# Sheet.net
KiCad netlist of a schematic drawn in Altium Designer
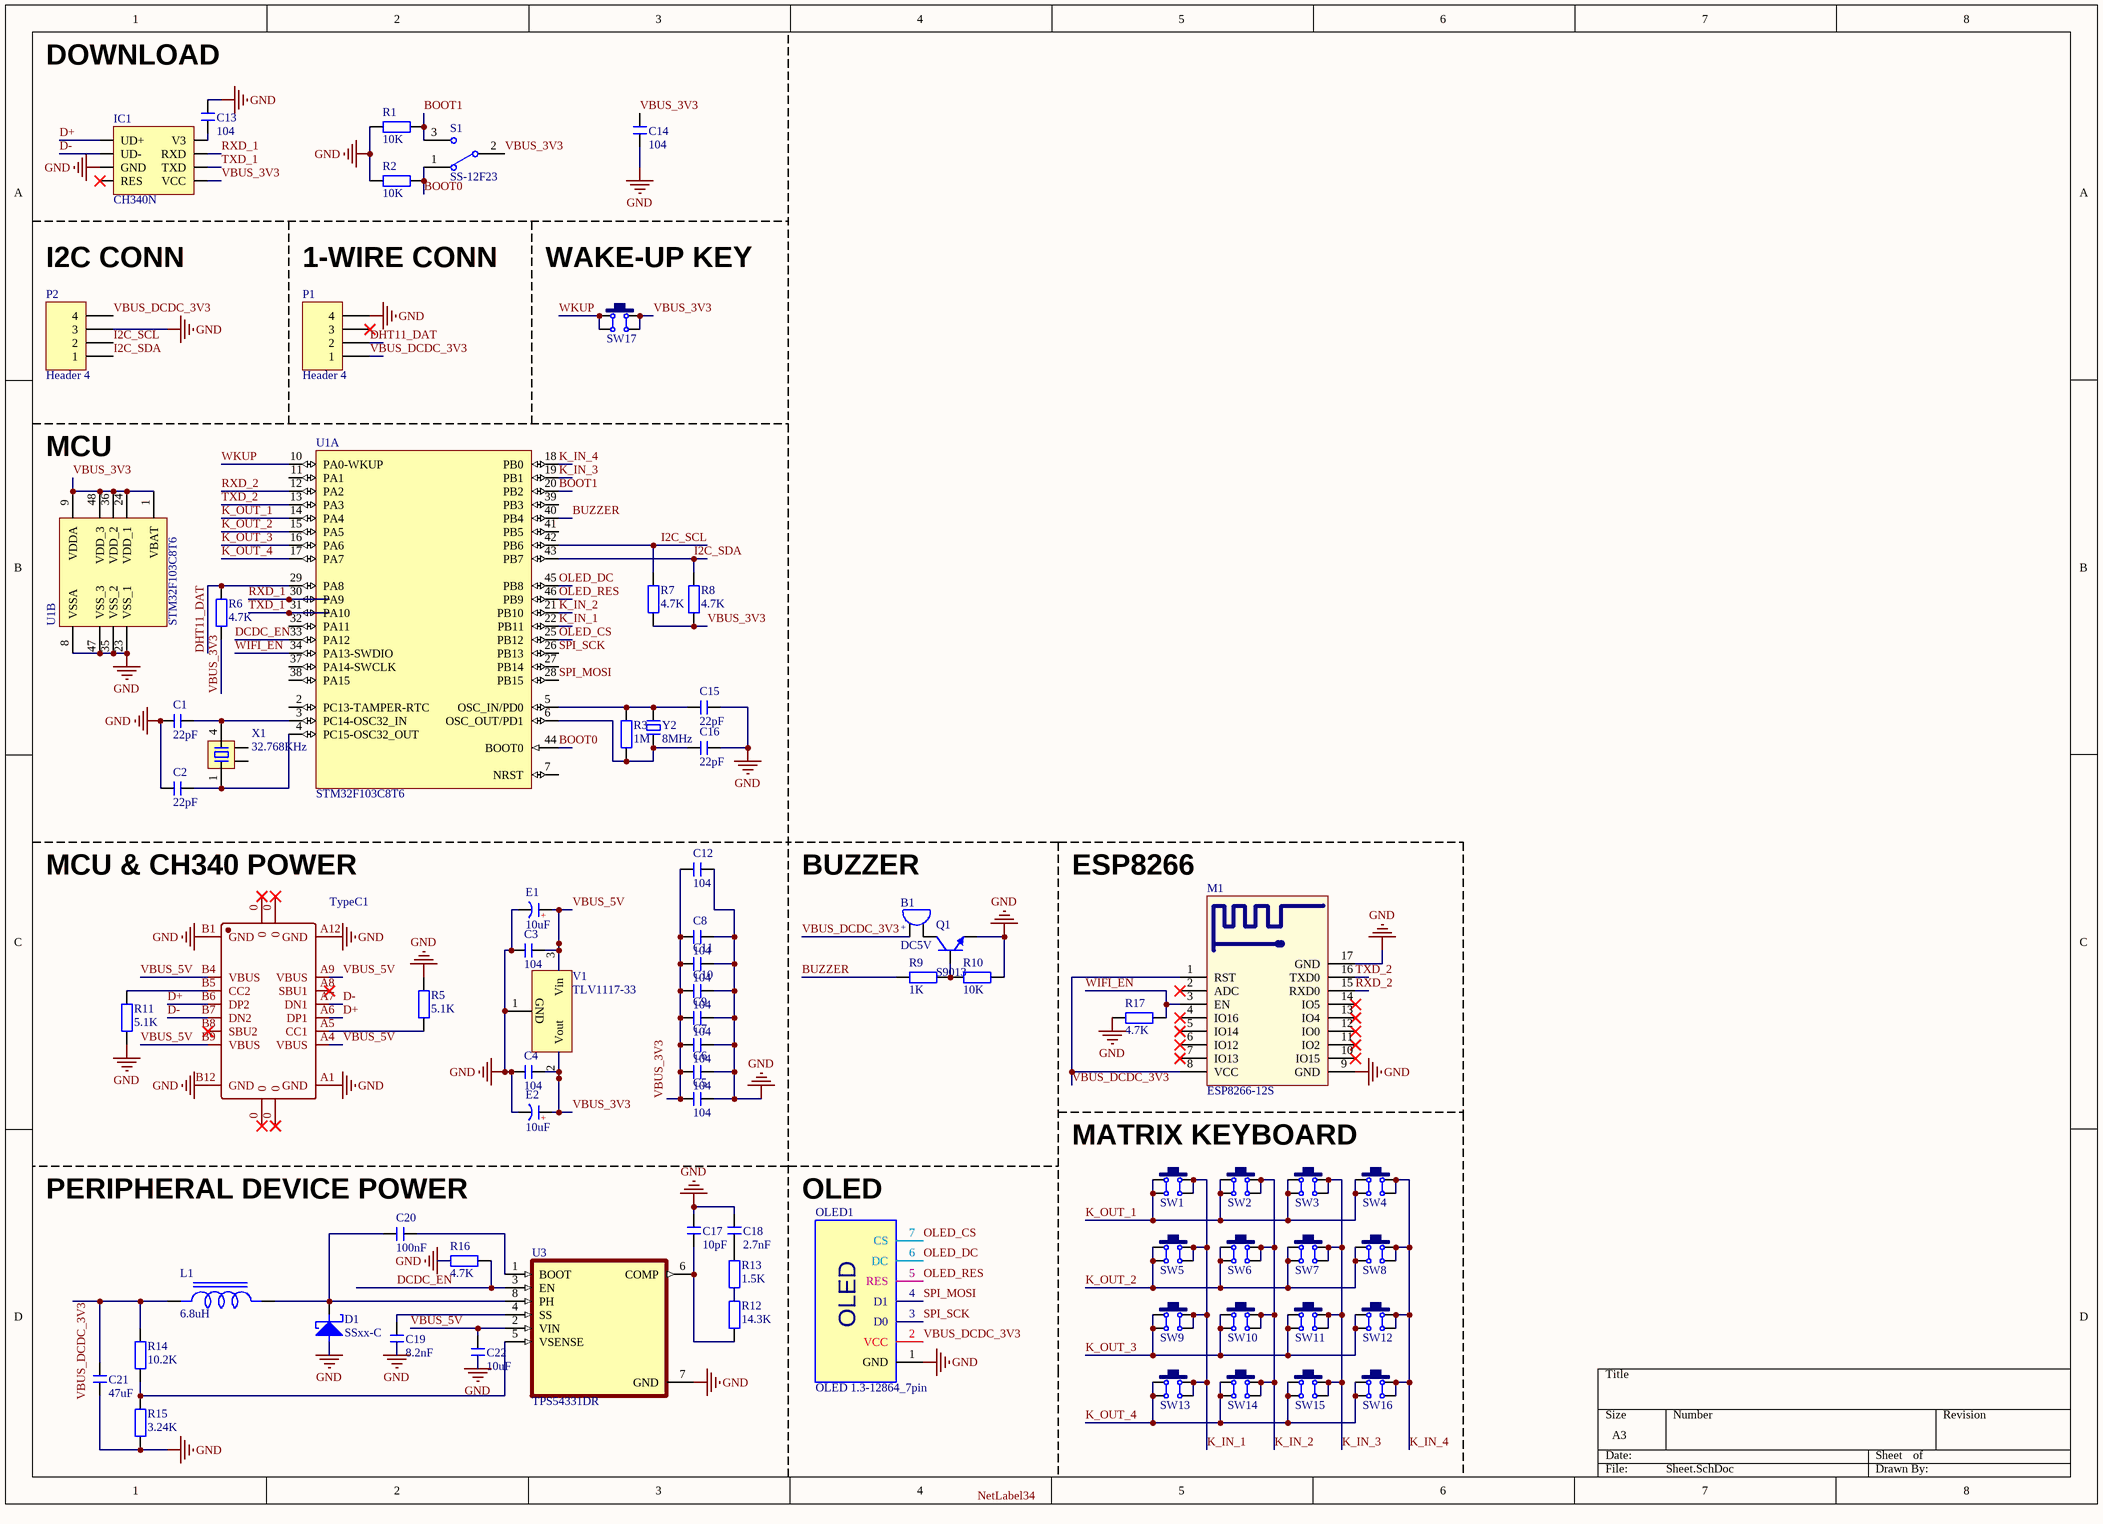
[diagram p0: Sheet.SchDoc]

(export (version "E")
  (design (tool "Eeschema 10.0.6"))
  (components
    (comp (ref "B1")
      (value "DC5V")
      (footprint "BEEP 5x9x5.5")
      (description "蜂鸣器")
      (fields (field (name "版权归属") "黎明电子style"))
      (libsource (lib "基地硬件部AD库3.01") (part "BEEP"))
    )
    (comp (ref "C1")
      (value "22pF")
      (footprint "C 0805")
      (description "无极性贴片电容")
      (fields (field (name "版权归属") "黎明电子style"))
      (libsource (lib "基地硬件部AD库3.01") (part "C"))
    )
    (comp (ref "C2")
      (value "22pF")
      (footprint "C 0805")
      (description "无极性贴片电容")
      (fields (field (name "版权归属") "黎明电子style"))
      (libsource (lib "基地硬件部AD库3.01") (part "C"))
    )
    (comp (ref "C3")
      (value "104")
      (footprint "C 0805")
      (description "无极性贴片电容")
      (fields (field (name "版权归属") "黎明电子style"))
      (libsource (lib "基地硬件部AD库3.01") (part "C"))
    )
    (comp (ref "C4")
      (value "104")
      (footprint "C 0805")
      (description "无极性贴片电容")
      (fields (field (name "版权归属") "黎明电子style"))
      (libsource (lib "基地硬件部AD库3.01") (part "C"))
    )
    (comp (ref "C5")
      (value "104")
      (footprint "C 0805")
      (description "无极性贴片电容")
      (fields (field (name "版权归属") "黎明电子style"))
      (libsource (lib "基地硬件部AD库3.01") (part "C"))
    )
    (comp (ref "C6")
      (value "104")
      (footprint "C 0805")
      (description "无极性贴片电容")
      (fields (field (name "版权归属") "黎明电子style"))
      (libsource (lib "基地硬件部AD库3.01") (part "C"))
    )
    (comp (ref "C7")
      (value "104")
      (footprint "C 0805")
      (description "无极性贴片电容")
      (fields (field (name "版权归属") "黎明电子style"))
      (libsource (lib "基地硬件部AD库3.01") (part "C"))
    )
    (comp (ref "C8")
      (value "104")
      (footprint "C 0805")
      (description "无极性贴片电容")
      (fields (field (name "版权归属") "黎明电子style"))
      (libsource (lib "基地硬件部AD库3.01") (part "C"))
    )
    (comp (ref "C9")
      (value "104")
      (footprint "C 0805")
      (description "无极性贴片电容")
      (fields (field (name "版权归属") "黎明电子style"))
      (libsource (lib "基地硬件部AD库3.01") (part "C"))
    )
    (comp (ref "C10")
      (value "104")
      (footprint "C 0805")
      (description "无极性贴片电容")
      (fields (field (name "版权归属") "黎明电子style"))
      (libsource (lib "基地硬件部AD库3.01") (part "C"))
    )
    (comp (ref "C11")
      (value "104")
      (footprint "C 0805")
      (description "无极性贴片电容")
      (fields (field (name "版权归属") "黎明电子style"))
      (libsource (lib "基地硬件部AD库3.01") (part "C"))
    )
    (comp (ref "C12")
      (value "104")
      (footprint "C 0805")
      (description "无极性贴片电容")
      (fields (field (name "版权归属") "黎明电子style"))
      (libsource (lib "基地硬件部AD库3.01") (part "C"))
    )
    (comp (ref "C13")
      (value "104")
      (footprint "C 0805")
      (description "无极性贴片电容")
      (fields (field (name "版权归属") "黎明电子style"))
      (libsource (lib "基地硬件部AD库3.01") (part "C"))
    )
    (comp (ref "C14")
      (value "104")
      (footprint "C 0805")
      (description "无极性贴片电容")
      (fields (field (name "版权归属") "黎明电子style"))
      (libsource (lib "基地硬件部AD库3.01") (part "C"))
    )
    (comp (ref "C15")
      (value "22pF")
      (footprint "C 0805")
      (description "无极性贴片电容")
      (fields (field (name "版权归属") "黎明电子style"))
      (libsource (lib "基地硬件部AD库3.01") (part "C"))
    )
    (comp (ref "C16")
      (value "22pF")
      (footprint "C 0805")
      (description "无极性贴片电容")
      (fields (field (name "版权归属") "黎明电子style"))
      (libsource (lib "基地硬件部AD库3.01") (part "C"))
    )
    (comp (ref "C17")
      (value "10pF")
      (footprint "C 0805")
      (description "无极性贴片电容")
      (fields (field (name "版权归属") "黎明电子style"))
      (libsource (lib "基地硬件部AD库3.01") (part "C"))
    )
    (comp (ref "C18")
      (value "2.7nF")
      (footprint "C 0805")
      (description "无极性贴片电容")
      (fields (field (name "版权归属") "黎明电子style"))
      (libsource (lib "基地硬件部AD库3.01") (part "C"))
    )
    (comp (ref "C19")
      (value "8.2nF")
      (footprint "C 0805")
      (description "无极性贴片电容")
      (fields (field (name "版权归属") "黎明电子style"))
      (libsource (lib "基地硬件部AD库3.01") (part "C"))
    )
    (comp (ref "C20")
      (value "100nF")
      (footprint "C 0805")
      (description "无极性贴片电容")
      (fields (field (name "版权归属") "黎明电子style"))
      (libsource (lib "基地硬件部AD库3.01") (part "C"))
    )
    (comp (ref "C21")
      (value "47uF")
      (footprint "C 0805")
      (description "无极性贴片电容")
      (fields (field (name "版权归属") "黎明电子style"))
      (libsource (lib "基地硬件部AD库3.01") (part "C"))
    )
    (comp (ref "C22")
      (value "10uF")
      (footprint "C 0805")
      (description "无极性贴片电容")
      (fields (field (name "版权归属") "黎明电子style"))
      (libsource (lib "基地硬件部AD库3.01") (part "C"))
    )
    (comp (ref "D1")
      (value "SSxx-C")
      (footprint "SMA")
      (description "肖特基二极管-贴片")
      (libsource (lib "基地硬件部AD库3.01") (part "SSxx-C"))
    )
    (comp (ref "E1")
      (value "10uF")
      (footprint "CD A(3216)")
      (description "贴片钽电容")
      (fields (field (name "版权归属") "黎明电子style"))
      (libsource (lib "基地硬件部AD库3.01") (part "C-CD"))
    )
    (comp (ref "E2")
      (value "10uF")
      (footprint "CD A(3216)")
      (description "贴片钽电容")
      (fields (field (name "版权归属") "黎明电子style"))
      (libsource (lib "基地硬件部AD库3.01") (part "C-CD"))
    )
    (comp (ref "IC1")
      (value "CH340N")
      (footprint "SOP8_N")
      (description "串口转USB")
      (fields (field (name "版权归属") "黎明电子style"))
      (libsource (lib "基地硬件部AD库3.01") (part "CH340N"))
    )
    (comp (ref "L1")
      (value "6.8uH")
      (footprint "IND_SRR4818A-6R8Y")
      (fields (field (name "MP") "SRR4818A-6R8Y"))
      (libsource (lib "SRR4818A-6R8Y") (part "SRR4818A-6R8Y"))
    )
    (comp (ref "M1")
      (value "ESP8266-12S")
      (footprint "ESP-12S Module")
      (description "串口WIFI模块，ESP8266-12S")
      (libsource (lib "基地硬件部AD库3.01") (part "ESP8266-12S"))
    )
    (comp (ref "OLED1")
      (value "OLED 1.3-12864_7pin")
      (footprint "OLED 1.3-12864_7pin")
      (description "OLED-SPI")
      (libsource (lib "基地硬件部AD库3.01") (part "OLED-1.3-SPI"))
    )
    (comp (ref "P1")
      (value "Header 4")
      (footprint "HDR1X4")
      (description "Header, 4-Pin")
      (fields (field (name "PUBLISHER") "Altium Limited"))
      (libsource (lib "Miscellaneous Connectors") (part "Header 4"))
    )
    (comp (ref "P2")
      (value "Header 4")
      (footprint "HDR1X4")
      (description "Header, 4-Pin")
      (fields (field (name "PUBLISHER") "Altium Limited"))
      (libsource (lib "Miscellaneous Connectors") (part "Header 4"))
    )
    (comp (ref "Q1")
      (value "S9013")
      (footprint "SOT23-3N")
      (description "低频放大-NPN型")
      (fields (field (name "版权归属") "源创客"))
      (libsource (lib "基地硬件部AD库3.01") (part "9013-SMD"))
    )
    (comp (ref "R1")
      (value "10K")
      (footprint "R 0805")
      (description "贴片电阻")
      (fields (field (name "版权归属") "黎明电子style"))
      (libsource (lib "基地硬件部AD库3.01") (part "R"))
    )
    (comp (ref "R2")
      (value "10K")
      (footprint "R 0805")
      (description "贴片电阻")
      (fields (field (name "版权归属") "黎明电子style"))
      (libsource (lib "基地硬件部AD库3.01") (part "R"))
    )
    (comp (ref "R3")
      (value "1M")
      (footprint "R 0805")
      (description "贴片电阻")
      (fields (field (name "版权归属") "黎明电子style"))
      (libsource (lib "基地硬件部AD库3.01") (part "R"))
    )
    (comp (ref "R5")
      (value "5.1K")
      (footprint "R 0805")
      (description "贴片电阻")
      (fields (field (name "版权归属") "黎明电子style"))
      (libsource (lib "基地硬件部AD库3.01") (part "R"))
    )
    (comp (ref "R6")
      (value "4.7K")
      (footprint "R 0805")
      (description "贴片电阻")
      (fields (field (name "版权归属") "黎明电子style"))
      (libsource (lib "基地硬件部AD库3.01") (part "R"))
    )
    (comp (ref "R7")
      (value "4.7K")
      (footprint "R 0805")
      (description "贴片电阻")
      (fields (field (name "版权归属") "黎明电子style"))
      (libsource (lib "基地硬件部AD库3.01") (part "R"))
    )
    (comp (ref "R8")
      (value "4.7K")
      (footprint "R 0805")
      (description "贴片电阻")
      (fields (field (name "版权归属") "黎明电子style"))
      (libsource (lib "基地硬件部AD库3.01") (part "R"))
    )
    (comp (ref "R9")
      (value "1K")
      (footprint "R 0805")
      (description "贴片电阻")
      (fields (field (name "版权归属") "黎明电子style"))
      (libsource (lib "基地硬件部AD库3.01") (part "R"))
    )
    (comp (ref "R10")
      (value "10K")
      (footprint "R 0805")
      (description "贴片电阻")
      (fields (field (name "版权归属") "黎明电子style"))
      (libsource (lib "基地硬件部AD库3.01") (part "R"))
    )
    (comp (ref "R11")
      (value "5.1K")
      (footprint "R 0805")
      (description "贴片电阻")
      (fields (field (name "版权归属") "黎明电子style"))
      (libsource (lib "基地硬件部AD库3.01") (part "R"))
    )
    (comp (ref "R12")
      (value "14.3K")
      (footprint "R 0805")
      (description "贴片电阻")
      (fields (field (name "版权归属") "黎明电子style"))
      (libsource (lib "基地硬件部AD库3.01") (part "R"))
    )
    (comp (ref "R13")
      (value "1.5K")
      (footprint "R 0805")
      (description "贴片电阻")
      (fields (field (name "版权归属") "黎明电子style"))
      (libsource (lib "基地硬件部AD库3.01") (part "R"))
    )
    (comp (ref "R14")
      (value "10.2K")
      (footprint "R 0805")
      (description "贴片电阻")
      (fields (field (name "版权归属") "黎明电子style"))
      (libsource (lib "基地硬件部AD库3.01") (part "R"))
    )
    (comp (ref "R15")
      (value "3.24K")
      (footprint "R 0805")
      (description "贴片电阻")
      (fields (field (name "版权归属") "黎明电子style"))
      (libsource (lib "基地硬件部AD库3.01") (part "R"))
    )
    (comp (ref "R16")
      (value "4.7K")
      (footprint "R 0805")
      (description "贴片电阻")
      (fields (field (name "版权归属") "黎明电子style"))
      (libsource (lib "基地硬件部AD库3.01") (part "R"))
    )
    (comp (ref "R17")
      (value "4.7K")
      (footprint "R 0805")
      (description "贴片电阻")
      (fields (field (name "版权归属") "黎明电子style"))
      (libsource (lib "基地硬件部AD库3.01") (part "R"))
    )
    (comp (ref "S1")
      (value "SS-12F23")
      (footprint "MSK-12C01-07")
      (description "1路波动开关")
      (fields (field (name "版权归属") "黎明电子style"))
      (libsource (lib "基地硬件部AD库3.01") (part "SSW-1P"))
    )
    (comp (ref "SW1")
      (value "6x6x5")
      (footprint "TSW SMD-6*6*4.3")
      (description "贴片6x6轻触开关")
      (fields (field (name "版权归属") "黎明电子style"))
      (libsource (lib "基地硬件部AD库3.01") (part "TSW SMD-6x6"))
    )
    (comp (ref "SW2")
      (value "6x6x5")
      (footprint "TSW SMD-6*6*4.3")
      (description "贴片6x6轻触开关")
      (fields (field (name "版权归属") "黎明电子style"))
      (libsource (lib "基地硬件部AD库3.01") (part "TSW SMD-6x6"))
    )
    (comp (ref "SW3")
      (value "6x6x5")
      (footprint "TSW SMD-6*6*4.3")
      (description "贴片6x6轻触开关")
      (fields (field (name "版权归属") "黎明电子style"))
      (libsource (lib "基地硬件部AD库3.01") (part "TSW SMD-6x6"))
    )
    (comp (ref "SW4")
      (value "6x6x5")
      (footprint "TSW SMD-6*6*4.3")
      (description "贴片6x6轻触开关")
      (fields (field (name "版权归属") "黎明电子style"))
      (libsource (lib "基地硬件部AD库3.01") (part "TSW SMD-6x6"))
    )
    (comp (ref "SW5")
      (value "6x6x5")
      (footprint "TSW SMD-6*6*4.3")
      (description "贴片6x6轻触开关")
      (fields (field (name "版权归属") "黎明电子style"))
      (libsource (lib "基地硬件部AD库3.01") (part "TSW SMD-6x6"))
    )
    (comp (ref "SW6")
      (value "6x6x5")
      (footprint "TSW SMD-6*6*4.3")
      (description "贴片6x6轻触开关")
      (fields (field (name "版权归属") "黎明电子style"))
      (libsource (lib "基地硬件部AD库3.01") (part "TSW SMD-6x6"))
    )
    (comp (ref "SW7")
      (value "6x6x5")
      (footprint "TSW SMD-6*6*4.3")
      (description "贴片6x6轻触开关")
      (fields (field (name "版权归属") "黎明电子style"))
      (libsource (lib "基地硬件部AD库3.01") (part "TSW SMD-6x6"))
    )
    (comp (ref "SW8")
      (value "6x6x5")
      (footprint "TSW SMD-6*6*4.3")
      (description "贴片6x6轻触开关")
      (fields (field (name "版权归属") "黎明电子style"))
      (libsource (lib "基地硬件部AD库3.01") (part "TSW SMD-6x6"))
    )
    (comp (ref "SW9")
      (value "6x6x5")
      (footprint "TSW SMD-6*6*4.3")
      (description "贴片6x6轻触开关")
      (fields (field (name "版权归属") "黎明电子style"))
      (libsource (lib "基地硬件部AD库3.01") (part "TSW SMD-6x6"))
    )
    (comp (ref "SW10")
      (value "6x6x5")
      (footprint "TSW SMD-6*6*4.3")
      (description "贴片6x6轻触开关")
      (fields (field (name "版权归属") "黎明电子style"))
      (libsource (lib "基地硬件部AD库3.01") (part "TSW SMD-6x6"))
    )
    (comp (ref "SW11")
      (value "6x6x5")
      (footprint "TSW SMD-6*6*4.3")
      (description "贴片6x6轻触开关")
      (fields (field (name "版权归属") "黎明电子style"))
      (libsource (lib "基地硬件部AD库3.01") (part "TSW SMD-6x6"))
    )
    (comp (ref "SW12")
      (value "6x6x5")
      (footprint "TSW SMD-6*6*4.3")
      (description "贴片6x6轻触开关")
      (fields (field (name "版权归属") "黎明电子style"))
      (libsource (lib "基地硬件部AD库3.01") (part "TSW SMD-6x6"))
    )
    (comp (ref "SW13")
      (value "6x6x5")
      (footprint "TSW SMD-6*6*4.3")
      (description "贴片6x6轻触开关")
      (fields (field (name "版权归属") "黎明电子style"))
      (libsource (lib "基地硬件部AD库3.01") (part "TSW SMD-6x6"))
    )
    (comp (ref "SW14")
      (value "6x6x5")
      (footprint "TSW SMD-6*6*4.3")
      (description "贴片6x6轻触开关")
      (fields (field (name "版权归属") "黎明电子style"))
      (libsource (lib "基地硬件部AD库3.01") (part "TSW SMD-6x6"))
    )
    (comp (ref "SW15")
      (value "6x6x5")
      (footprint "TSW SMD-6*6*4.3")
      (description "贴片6x6轻触开关")
      (fields (field (name "版权归属") "黎明电子style"))
      (libsource (lib "基地硬件部AD库3.01") (part "TSW SMD-6x6"))
    )
    (comp (ref "SW16")
      (value "6x6x5")
      (footprint "TSW SMD-6*6*4.3")
      (description "贴片6x6轻触开关")
      (fields (field (name "版权归属") "黎明电子style"))
      (libsource (lib "基地硬件部AD库3.01") (part "TSW SMD-6x6"))
    )
    (comp (ref "SW17")
      (value "6x6x5")
      (footprint "TSW SMD-6*6*4.3")
      (description "贴片6x6轻触开关")
      (fields (field (name "版权归属") "黎明电子style"))
      (libsource (lib "基地硬件部AD库3.01") (part "TSW SMD-6x6"))
    )
    (comp (ref "TypeC1")
      (value "TypeC-16pin")
      (footprint "typeC-16pin")
      (description "USB-C-16Pin")
      (libsource (lib "基地硬件部AD库3.01") (part "TypeC-16pin"))
    )
    (comp (ref "U1")
      (value "STM32F103C8T6")
      (footprint "LQFP48 7X7_N")
      (description "Pin:48/IO:36")
      (fields (field (name "版权归属") "校基地硬件部"))
      (libsource (lib "") (part "STM32F103C8Tx_1"))
    )
    (comp (ref "U3")
      (value "TPS54331DR")
      (footprint "SOIC127P599X175-8N")
      (description "3.5V to 28V Input, 3A, 570kHz Step-Down Converter with Eco-mode 8-SOIC -40 to 150")
      (fields (field (name "MF") "Texas Instruments"))
      (libsource (lib "TPS54331DR") (part "TPS54331DR"))
    )
    (comp (ref "V1")
      (value "TLV1117-33")
      (footprint "SOT223_L")
      (description "三端稳压芯片")
      (fields (field (name "版权归属") "源创客"))
      (libsource (lib "基地硬件部AD库3.01") (part "AMS1117"))
    )
    (comp (ref "X1")
      (value "32.768KHz")
      (footprint "OSC MC-146")
      (description "MC系列4脚晶振")
      (fields (field (name "版权归属") "源创客"))
      (libsource (lib "基地硬件部AD库3.01") (part "XTAL-MC-4P"))
    )
    (comp (ref "Y2")
      (value "8MHz")
      (footprint "OSC HC-49SMD")
      (description "2脚无源脚晶振")
      (fields (field (name "版权归属") "源创客"))
      (libsource (lib "基地硬件部AD库3.01") (part "XTAL-2P"))
    )
  )
  (nets
    (net (code "1") (name "/BOOT0") (class "Default")
      (node (ref "R2") (pin "2") (pinfunction "2_2") (pintype "passive"))
      (node (ref "S1") (pin "1") (pinfunction "1_1") (pintype "passive"))
      (node (ref "U1") (pin "44") (pinfunction "BOOT0_44") (pintype "input"))
    )
    (net (code "2") (name "/BOOT1") (class "Default")
      (node (ref "R1") (pin "2") (pinfunction "2_2") (pintype "passive"))
      (node (ref "S1") (pin "3") (pinfunction "3_3") (pintype "passive"))
      (node (ref "U1") (pin "20") (pinfunction "PB2_20") (pintype "bidirectional"))
    )
    (net (code "3") (name "/BUZZER") (class "Default")
      (node (ref "R9") (pin "2") (pinfunction "2_2") (pintype "passive"))
      (node (ref "U1") (pin "40") (pinfunction "PB4_40") (pintype "bidirectional"))
    )
    (net (code "4") (name "/D+") (class "Default")
      (node (ref "IC1") (pin "1") (pinfunction "UD+_1") (pintype "passive"))
      (node (ref "TypeC1") (pin "A6") (pinfunction "DP1_A6") (pintype "passive"))
      (node (ref "TypeC1") (pin "B6") (pinfunction "DP2_B6") (pintype "passive"))
    )
    (net (code "5") (name "/D-") (class "Default")
      (node (ref "IC1") (pin "2") (pinfunction "UD-_2") (pintype "passive"))
      (node (ref "TypeC1") (pin "A7") (pinfunction "DN1_A7") (pintype "passive"))
      (node (ref "TypeC1") (pin "B7") (pinfunction "DN2_B7") (pintype "passive"))
    )
    (net (code "6") (name "/DCDC_EN") (class "Default")
      (node (ref "R16") (pin "2") (pinfunction "2_2") (pintype "passive"))
      (node (ref "U1") (pin "33") (pinfunction "PA12_33") (pintype "bidirectional"))
      (node (ref "U3") (pin "3") (pinfunction "EN_3") (pintype "input"))
    )
    (net (code "7") (name "/DHT11_DAT") (class "Default")
      (node (ref "P1") (pin "2") (pinfunction "2_2") (pintype "passive"))
      (node (ref "R6") (pin "2") (pinfunction "2_2") (pintype "passive"))
      (node (ref "U1") (pin "29") (pinfunction "PA8_29") (pintype "bidirectional"))
    )
    (net (code "8") (name "/I2C_SCL") (class "Default")
      (node (ref "P2") (pin "2") (pinfunction "2_2") (pintype "passive"))
      (node (ref "R7") (pin "2") (pinfunction "2_2") (pintype "passive"))
      (node (ref "U1") (pin "42") (pinfunction "PB6_42") (pintype "bidirectional"))
    )
    (net (code "9") (name "/I2C_SDA") (class "Default")
      (node (ref "P2") (pin "1") (pinfunction "1_1") (pintype "passive"))
      (node (ref "R8") (pin "2") (pinfunction "2_2") (pintype "passive"))
      (node (ref "U1") (pin "43") (pinfunction "PB7_43") (pintype "bidirectional"))
    )
    (net (code "10") (name "/K_IN_1") (class "Default")
      (node (ref "SW1") (pin "2") (pinfunction "2_2") (pintype "passive"))
      (node (ref "SW1") (pin "3") (pinfunction "3_3") (pintype "passive"))
      (node (ref "SW13") (pin "2") (pinfunction "2_2") (pintype "passive"))
      (node (ref "SW13") (pin "3") (pinfunction "3_3") (pintype "passive"))
      (node (ref "SW5") (pin "2") (pinfunction "2_2") (pintype "passive"))
      (node (ref "SW5") (pin "3") (pinfunction "3_3") (pintype "passive"))
      (node (ref "SW9") (pin "2") (pinfunction "2_2") (pintype "passive"))
      (node (ref "SW9") (pin "3") (pinfunction "3_3") (pintype "passive"))
      (node (ref "U1") (pin "22") (pinfunction "PB11_22") (pintype "bidirectional"))
    )
    (net (code "11") (name "/K_IN_2") (class "Default")
      (node (ref "SW10") (pin "2") (pinfunction "2_2") (pintype "passive"))
      (node (ref "SW10") (pin "3") (pinfunction "3_3") (pintype "passive"))
      (node (ref "SW14") (pin "2") (pinfunction "2_2") (pintype "passive"))
      (node (ref "SW14") (pin "3") (pinfunction "3_3") (pintype "passive"))
      (node (ref "SW2") (pin "2") (pinfunction "2_2") (pintype "passive"))
      (node (ref "SW2") (pin "3") (pinfunction "3_3") (pintype "passive"))
      (node (ref "SW6") (pin "2") (pinfunction "2_2") (pintype "passive"))
      (node (ref "SW6") (pin "3") (pinfunction "3_3") (pintype "passive"))
      (node (ref "U1") (pin "21") (pinfunction "PB10_21") (pintype "bidirectional"))
    )
    (net (code "12") (name "/K_IN_3") (class "Default")
      (node (ref "SW11") (pin "2") (pinfunction "2_2") (pintype "passive"))
      (node (ref "SW11") (pin "3") (pinfunction "3_3") (pintype "passive"))
      (node (ref "SW15") (pin "2") (pinfunction "2_2") (pintype "passive"))
      (node (ref "SW15") (pin "3") (pinfunction "3_3") (pintype "passive"))
      (node (ref "SW3") (pin "2") (pinfunction "2_2") (pintype "passive"))
      (node (ref "SW3") (pin "3") (pinfunction "3_3") (pintype "passive"))
      (node (ref "SW7") (pin "2") (pinfunction "2_2") (pintype "passive"))
      (node (ref "SW7") (pin "3") (pinfunction "3_3") (pintype "passive"))
      (node (ref "U1") (pin "19") (pinfunction "PB1_19") (pintype "bidirectional"))
    )
    (net (code "13") (name "/K_IN_4") (class "Default")
      (node (ref "SW12") (pin "2") (pinfunction "2_2") (pintype "passive"))
      (node (ref "SW12") (pin "3") (pinfunction "3_3") (pintype "passive"))
      (node (ref "SW16") (pin "2") (pinfunction "2_2") (pintype "passive"))
      (node (ref "SW16") (pin "3") (pinfunction "3_3") (pintype "passive"))
      (node (ref "SW4") (pin "2") (pinfunction "2_2") (pintype "passive"))
      (node (ref "SW4") (pin "3") (pinfunction "3_3") (pintype "passive"))
      (node (ref "SW8") (pin "2") (pinfunction "2_2") (pintype "passive"))
      (node (ref "SW8") (pin "3") (pinfunction "3_3") (pintype "passive"))
      (node (ref "U1") (pin "18") (pinfunction "PB0_18") (pintype "bidirectional"))
    )
    (net (code "14") (name "/K_OUT_1") (class "Default")
      (node (ref "SW1") (pin "1") (pinfunction "1_1") (pintype "passive"))
      (node (ref "SW1") (pin "4") (pinfunction "4_4") (pintype "passive"))
      (node (ref "SW2") (pin "1") (pinfunction "1_1") (pintype "passive"))
      (node (ref "SW2") (pin "4") (pinfunction "4_4") (pintype "passive"))
      (node (ref "SW3") (pin "1") (pinfunction "1_1") (pintype "passive"))
      (node (ref "SW3") (pin "4") (pinfunction "4_4") (pintype "passive"))
      (node (ref "SW4") (pin "1") (pinfunction "1_1") (pintype "passive"))
      (node (ref "SW4") (pin "4") (pinfunction "4_4") (pintype "passive"))
      (node (ref "U1") (pin "14") (pinfunction "PA4_14") (pintype "bidirectional"))
    )
    (net (code "15") (name "/K_OUT_2") (class "Default")
      (node (ref "SW5") (pin "1") (pinfunction "1_1") (pintype "passive"))
      (node (ref "SW5") (pin "4") (pinfunction "4_4") (pintype "passive"))
      (node (ref "SW6") (pin "1") (pinfunction "1_1") (pintype "passive"))
      (node (ref "SW6") (pin "4") (pinfunction "4_4") (pintype "passive"))
      (node (ref "SW7") (pin "1") (pinfunction "1_1") (pintype "passive"))
      (node (ref "SW7") (pin "4") (pinfunction "4_4") (pintype "passive"))
      (node (ref "SW8") (pin "1") (pinfunction "1_1") (pintype "passive"))
      (node (ref "SW8") (pin "4") (pinfunction "4_4") (pintype "passive"))
      (node (ref "U1") (pin "15") (pinfunction "PA5_15") (pintype "bidirectional"))
    )
    (net (code "16") (name "/K_OUT_3") (class "Default")
      (node (ref "SW10") (pin "1") (pinfunction "1_1") (pintype "passive"))
      (node (ref "SW10") (pin "4") (pinfunction "4_4") (pintype "passive"))
      (node (ref "SW11") (pin "1") (pinfunction "1_1") (pintype "passive"))
      (node (ref "SW11") (pin "4") (pinfunction "4_4") (pintype "passive"))
      (node (ref "SW12") (pin "1") (pinfunction "1_1") (pintype "passive"))
      (node (ref "SW12") (pin "4") (pinfunction "4_4") (pintype "passive"))
      (node (ref "SW9") (pin "1") (pinfunction "1_1") (pintype "passive"))
      (node (ref "SW9") (pin "4") (pinfunction "4_4") (pintype "passive"))
      (node (ref "U1") (pin "16") (pinfunction "PA6_16") (pintype "bidirectional"))
    )
    (net (code "17") (name "/K_OUT_4") (class "Default")
      (node (ref "SW13") (pin "1") (pinfunction "1_1") (pintype "passive"))
      (node (ref "SW13") (pin "4") (pinfunction "4_4") (pintype "passive"))
      (node (ref "SW14") (pin "1") (pinfunction "1_1") (pintype "passive"))
      (node (ref "SW14") (pin "4") (pinfunction "4_4") (pintype "passive"))
      (node (ref "SW15") (pin "1") (pinfunction "1_1") (pintype "passive"))
      (node (ref "SW15") (pin "4") (pinfunction "4_4") (pintype "passive"))
      (node (ref "SW16") (pin "1") (pinfunction "1_1") (pintype "passive"))
      (node (ref "SW16") (pin "4") (pinfunction "4_4") (pintype "passive"))
      (node (ref "U1") (pin "17") (pinfunction "PA7_17") (pintype "bidirectional"))
    )
    (net (code "19") (name "/OLED_CS") (class "Default")
      (node (ref "OLED1") (pin "7") (pinfunction "CS_7") (pintype "passive"))
      (node (ref "U1") (pin "25") (pinfunction "PB12_25") (pintype "bidirectional"))
    )
    (net (code "20") (name "/OLED_DC") (class "Default")
      (node (ref "OLED1") (pin "6") (pinfunction "DC_6") (pintype "passive"))
      (node (ref "U1") (pin "45") (pinfunction "PB8_45") (pintype "bidirectional"))
    )
    (net (code "21") (name "/OLED_RES") (class "Default")
      (node (ref "OLED1") (pin "5") (pinfunction "RES_5") (pintype "passive"))
      (node (ref "U1") (pin "46") (pinfunction "PB9_46") (pintype "bidirectional"))
    )
    (net (code "22") (name "/RXD_1") (class "Default")
      (node (ref "IC1") (pin "7") (pinfunction "RXD_7") (pintype "passive"))
      (node (ref "U1") (pin "30") (pinfunction "PA9_30") (pintype "bidirectional"))
    )
    (net (code "23") (name "/RXD_2") (class "Default")
      (node (ref "M1") (pin "15") (pinfunction "RXD0_15") (pintype "passive"))
      (node (ref "U1") (pin "12") (pinfunction "PA2_12") (pintype "bidirectional"))
    )
    (net (code "24") (name "/SPI_MOSI") (class "Default")
      (node (ref "OLED1") (pin "4") (pinfunction "D1_4") (pintype "passive"))
      (node (ref "U1") (pin "28") (pinfunction "PB15_28") (pintype "bidirectional"))
    )
    (net (code "25") (name "/SPI_SCK") (class "Default")
      (node (ref "OLED1") (pin "3") (pinfunction "D0_3") (pintype "passive"))
      (node (ref "U1") (pin "26") (pinfunction "PB13_26") (pintype "bidirectional"))
    )
    (net (code "26") (name "/TXD_1") (class "Default")
      (node (ref "IC1") (pin "6") (pinfunction "TXD_6") (pintype "passive"))
      (node (ref "U1") (pin "31") (pinfunction "PA10_31") (pintype "bidirectional"))
    )
    (net (code "27") (name "/TXD_2") (class "Default")
      (node (ref "M1") (pin "16") (pinfunction "TXD0_16") (pintype "passive"))
      (node (ref "U1") (pin "13") (pinfunction "PA3_13") (pintype "bidirectional"))
    )
    (net (code "28") (name "/VBUS_3V3") (class "Default")
      (node (ref "C10") (pin "1") (pinfunction "1_1") (pintype "passive"))
      (node (ref "C11") (pin "1") (pinfunction "1_1") (pintype "passive"))
      (node (ref "C12") (pin "1") (pinfunction "1_1") (pintype "passive"))
      (node (ref "C14") (pin "1") (pinfunction "1_1") (pintype "passive"))
      (node (ref "C4") (pin "1") (pinfunction "1_1") (pintype "passive"))
      (node (ref "C5") (pin "1") (pinfunction "1_1") (pintype "passive"))
      (node (ref "C6") (pin "1") (pinfunction "1_1") (pintype "passive"))
      (node (ref "C7") (pin "1") (pinfunction "1_1") (pintype "passive"))
      (node (ref "C8") (pin "1") (pinfunction "1_1") (pintype "passive"))
      (node (ref "C9") (pin "1") (pinfunction "1_1") (pintype "passive"))
      (node (ref "E2") (pin "1") (pinfunction "A_1") (pintype "passive"))
      (node (ref "IC1") (pin "5") (pinfunction "VCC_5") (pintype "passive"))
      (node (ref "R6") (pin "1") (pinfunction "1_1") (pintype "passive"))
      (node (ref "R7") (pin "1") (pinfunction "1_1") (pintype "passive"))
      (node (ref "R8") (pin "1") (pinfunction "1_1") (pintype "passive"))
      (node (ref "S1") (pin "2") (pinfunction "2_2") (pintype "passive"))
      (node (ref "SW17") (pin "2") (pinfunction "2_2") (pintype "passive"))
      (node (ref "SW17") (pin "3") (pinfunction "3_3") (pintype "passive"))
      (node (ref "U1") (pin "1") (pinfunction "VBAT_1") (pintype "power_in"))
      (node (ref "U1") (pin "24") (pinfunction "VDD_1_24") (pintype "power_in"))
      (node (ref "U1") (pin "36") (pinfunction "VDD_2_36") (pintype "power_in"))
      (node (ref "U1") (pin "48") (pinfunction "VDD_3_48") (pintype "power_in"))
      (node (ref "U1") (pin "9") (pinfunction "VDDA_9") (pintype "power_in"))
      (node (ref "V1") (pin "2") (pinfunction "Vout_2") (pintype "passive"))
    )
    (net (code "29") (name "/VBUS_5V") (class "Default")
      (node (ref "C22") (pin "2") (pinfunction "2_2") (pintype "passive"))
      (node (ref "C3") (pin "1") (pinfunction "1_1") (pintype "passive"))
      (node (ref "E1") (pin "1") (pinfunction "A_1") (pintype "passive"))
      (node (ref "TypeC1") (pin "A4") (pinfunction "VBUS_A4") (pintype "passive"))
      (node (ref "TypeC1") (pin "A9") (pinfunction "VBUS_A9") (pintype "passive"))
      (node (ref "TypeC1") (pin "B4") (pinfunction "VBUS_B4") (pintype "passive"))
      (node (ref "TypeC1") (pin "B9") (pinfunction "VBUS_B9") (pintype "passive"))
      (node (ref "U3") (pin "2") (pinfunction "VIN_2") (pintype "input"))
      (node (ref "V1") (pin "3") (pinfunction "Vin_3") (pintype "passive"))
    )
    (net (code "30") (name "/VBUS_DCDC_3V3") (class "Default")
      (node (ref "B1") (pin "1") (pinfunction "1_1") (pintype "passive"))
      (node (ref "C21") (pin "2") (pinfunction "2_2") (pintype "passive"))
      (node (ref "L1") (pin "1") (pinfunction "1_1") (pintype "passive"))
      (node (ref "M1") (pin "1") (pinfunction "RST_1") (pintype "passive"))
      (node (ref "M1") (pin "8") (pinfunction "VCC_8") (pintype "passive"))
      (node (ref "OLED1") (pin "2") (pinfunction "VCC_2") (pintype "passive"))
      (node (ref "P1") (pin "1") (pinfunction "1_1") (pintype "passive"))
      (node (ref "P2") (pin "4") (pinfunction "4_4") (pintype "passive"))
      (node (ref "R14") (pin "1") (pinfunction "1_1") (pintype "passive"))
    )
    (net (code "31") (name "/WIFI_EN") (class "Default")
      (node (ref "M1") (pin "3") (pinfunction "EN_3") (pintype "passive"))
      (node (ref "R17") (pin "1") (pinfunction "1_1") (pintype "passive"))
      (node (ref "U1") (pin "34") (pinfunction "PA13-SWDIO_34") (pintype "bidirectional"))
    )
    (net (code "32") (name "/WKUP") (class "Default")
      (node (ref "SW17") (pin "1") (pinfunction "1_1") (pintype "passive"))
      (node (ref "SW17") (pin "4") (pinfunction "4_4") (pintype "passive"))
      (node (ref "U1") (pin "10") (pinfunction "PA0-WKUP_10") (pintype "bidirectional"))
    )
    (net (code "33") (name "GND") (class "Default")
      (node (ref "C1") (pin "2") (pinfunction "2_2") (pintype "passive"))
      (node (ref "C10") (pin "2") (pinfunction "2_2") (pintype "passive"))
      (node (ref "C11") (pin "2") (pinfunction "2_2") (pintype "passive"))
      (node (ref "C12") (pin "2") (pinfunction "2_2") (pintype "passive"))
      (node (ref "C13") (pin "1") (pinfunction "1_1") (pintype "passive"))
      (node (ref "C14") (pin "2") (pinfunction "2_2") (pintype "passive"))
      (node (ref "C15") (pin "1") (pinfunction "1_1") (pintype "passive"))
      (node (ref "C16") (pin "1") (pinfunction "1_1") (pintype "passive"))
      (node (ref "C17") (pin "2") (pinfunction "2_2") (pintype "passive"))
      (node (ref "C18") (pin "2") (pinfunction "2_2") (pintype "passive"))
      (node (ref "C19") (pin "1") (pinfunction "1_1") (pintype "passive"))
      (node (ref "C2") (pin "2") (pinfunction "2_2") (pintype "passive"))
      (node (ref "C21") (pin "1") (pinfunction "1_1") (pintype "passive"))
      (node (ref "C22") (pin "1") (pinfunction "1_1") (pintype "passive"))
      (node (ref "C3") (pin "2") (pinfunction "2_2") (pintype "passive"))
      (node (ref "C4") (pin "2") (pinfunction "2_2") (pintype "passive"))
      (node (ref "C5") (pin "2") (pinfunction "2_2") (pintype "passive"))
      (node (ref "C6") (pin "2") (pinfunction "2_2") (pintype "passive"))
      (node (ref "C7") (pin "2") (pinfunction "2_2") (pintype "passive"))
      (node (ref "C8") (pin "2") (pinfunction "2_2") (pintype "passive"))
      (node (ref "C9") (pin "2") (pinfunction "2_2") (pintype "passive"))
      (node (ref "D1") (pin "1") (pinfunction "A_1") (pintype "passive"))
      (node (ref "E1") (pin "2") (pinfunction "K_2") (pintype "passive"))
      (node (ref "E2") (pin "2") (pinfunction "K_2") (pintype "passive"))
      (node (ref "IC1") (pin "3") (pinfunction "GND_3") (pintype "passive"))
      (node (ref "M1") (pin "17") (pinfunction "GND_17") (pintype "passive"))
      (node (ref "M1") (pin "9") (pinfunction "GND_9") (pintype "passive"))
      (node (ref "OLED1") (pin "1") (pinfunction "GND_1") (pintype "passive"))
      (node (ref "P1") (pin "4") (pinfunction "4_4") (pintype "passive"))
      (node (ref "P2") (pin "3") (pinfunction "3_3") (pintype "passive"))
      (node (ref "Q1") (pin "2") (pinfunction "E_2") (pintype "passive"))
      (node (ref "R1") (pin "1") (pinfunction "1_1") (pintype "passive"))
      (node (ref "R10") (pin "1") (pinfunction "1_1") (pintype "passive"))
      (node (ref "R11") (pin "1") (pinfunction "1_1") (pintype "passive"))
      (node (ref "R15") (pin "2") (pinfunction "2_2") (pintype "passive"))
      (node (ref "R16") (pin "1") (pinfunction "1_1") (pintype "passive"))
      (node (ref "R17") (pin "2") (pinfunction "2_2") (pintype "passive"))
      (node (ref "R2") (pin "1") (pinfunction "1_1") (pintype "passive"))
      (node (ref "R5") (pin "1") (pinfunction "1_1") (pintype "passive"))
      (node (ref "TypeC1") (pin "A1") (pinfunction "GND_A1") (pintype "passive"))
      (node (ref "TypeC1") (pin "A12") (pinfunction "GND_A12") (pintype "passive"))
      (node (ref "TypeC1") (pin "B1") (pinfunction "GND_B1") (pintype "passive"))
      (node (ref "TypeC1") (pin "B12") (pinfunction "GND_B12") (pintype "passive"))
      (node (ref "U1") (pin "23") (pinfunction "VSS_1_23") (pintype "power_in"))
      (node (ref "U1") (pin "35") (pinfunction "VSS_2_35") (pintype "power_in"))
      (node (ref "U1") (pin "47") (pinfunction "VSS_3_47") (pintype "power_in"))
      (node (ref "U1") (pin "8") (pinfunction "VSSA_8") (pintype "power_in"))
      (node (ref "U3") (pin "7") (pinfunction "GND_7") (pintype "power_in"))
      (node (ref "V1") (pin "1") (pinfunction "GND_1") (pintype "passive"))
    )
    (net (code "34") (name "Net-(C18-Pad1)") (class "Default")
      (node (ref "C18") (pin "1") (pinfunction "1_1") (pintype "passive"))
      (node (ref "R13") (pin "1") (pinfunction "1_1") (pintype "passive"))
    )
    (net (code "35") (name "Net-(D1-K)") (class "Default")
      (node (ref "C20") (pin "1") (pinfunction "1_1") (pintype "passive"))
      (node (ref "D1") (pin "2") (pinfunction "K_2") (pintype "passive"))
      (node (ref "L1") (pin "2") (pinfunction "2_2") (pintype "passive"))
      (node (ref "U3") (pin "8") (pinfunction "PH_8") (pintype "input"))
    )
    (net (code "36") (name "Net-(IC1-V3)") (class "Default")
      (node (ref "C13") (pin "2") (pinfunction "2_2") (pintype "passive"))
      (node (ref "IC1") (pin "8") (pinfunction "V3_8") (pintype "passive"))
    )
    (net (code "37") (name "Net-(Q1-B)") (class "Default")
      (node (ref "Q1") (pin "1") (pinfunction "B_1") (pintype "passive"))
      (node (ref "R10") (pin "2") (pinfunction "2_2") (pintype "passive"))
      (node (ref "R9") (pin "1") (pinfunction "1_1") (pintype "passive"))
    )
    (net (code "38") (name "Net-(Q1-C)") (class "Default")
      (node (ref "B1") (pin "2") (pinfunction "2_2") (pintype "passive"))
      (node (ref "Q1") (pin "3") (pinfunction "C_3") (pintype "passive"))
    )
    (net (code "39") (name "Net-(R12-Pad1)") (class "Default")
      (node (ref "R12") (pin "1") (pinfunction "1_1") (pintype "passive"))
      (node (ref "R13") (pin "2") (pinfunction "2_2") (pintype "passive"))
    )
    (net (code "40") (name "Net-(TypeC1-CC1)") (class "Default")
      (node (ref "R5") (pin "2") (pinfunction "2_2") (pintype "passive"))
      (node (ref "TypeC1") (pin "A5") (pinfunction "CC1_A5") (pintype "passive"))
    )
    (net (code "41") (name "Net-(TypeC1-CC2)") (class "Default")
      (node (ref "R11") (pin "2") (pinfunction "2_2") (pintype "passive"))
      (node (ref "TypeC1") (pin "B5") (pinfunction "CC2_B5") (pintype "passive"))
    )
    (net (code "42") (name "Net-(U1A-OSC_IN{slash}PD0)") (class "Default")
      (node (ref "C15") (pin "2") (pinfunction "2_2") (pintype "passive"))
      (node (ref "R3") (pin "2") (pinfunction "2_2") (pintype "passive"))
      (node (ref "U1") (pin "5") (pinfunction "OSC_IN/PD0_5") (pintype "bidirectional"))
      (node (ref "Y2") (pin "2") (pinfunction "2_2") (pintype "passive"))
    )
    (net (code "43") (name "Net-(U1A-OSC_OUT{slash}PD1)") (class "Default")
      (node (ref "C16") (pin "2") (pinfunction "2_2") (pintype "passive"))
      (node (ref "R3") (pin "1") (pinfunction "1_1") (pintype "passive"))
      (node (ref "U1") (pin "6") (pinfunction "OSC_OUT/PD1_6") (pintype "bidirectional"))
      (node (ref "Y2") (pin "1") (pinfunction "1_1") (pintype "passive"))
    )
    (net (code "44") (name "Net-(U1A-PC14-OSC32_IN)") (class "Default")
      (node (ref "C1") (pin "1") (pinfunction "1_1") (pintype "passive"))
      (node (ref "U1") (pin "3") (pinfunction "PC14-OSC32_IN_3") (pintype "bidirectional"))
      (node (ref "X1") (pin "4") (pinfunction "4_4") (pintype "passive"))
    )
    (net (code "45") (name "Net-(U1A-PC15-OSC32_OUT)") (class "Default")
      (node (ref "C2") (pin "1") (pinfunction "1_1") (pintype "passive"))
      (node (ref "U1") (pin "4") (pinfunction "PC15-OSC32_OUT_4") (pintype "bidirectional"))
      (node (ref "X1") (pin "1") (pinfunction "1_1") (pintype "passive"))
    )
    (net (code "46") (name "Net-(U3-BOOT)") (class "Default")
      (node (ref "C20") (pin "2") (pinfunction "2_2") (pintype "passive"))
      (node (ref "U3") (pin "1") (pinfunction "BOOT_1") (pintype "input"))
    )
    (net (code "47") (name "Net-(U3-COMP)") (class "Default")
      (node (ref "C17") (pin "1") (pinfunction "1_1") (pintype "passive"))
      (node (ref "R12") (pin "2") (pinfunction "2_2") (pintype "passive"))
      (node (ref "U3") (pin "6") (pinfunction "COMP_6") (pintype "output"))
    )
    (net (code "48") (name "Net-(U3-SS)") (class "Default")
      (node (ref "C19") (pin "2") (pinfunction "2_2") (pintype "passive"))
      (node (ref "U3") (pin "4") (pinfunction "SS_4") (pintype "input"))
    )
    (net (code "49") (name "Net-(U3-VSENSE)") (class "Default")
      (node (ref "R14") (pin "2") (pinfunction "2_2") (pintype "passive"))
      (node (ref "R15") (pin "1") (pinfunction "1_1") (pintype "passive"))
      (node (ref "U3") (pin "5") (pinfunction "VSENSE_5") (pintype "input"))
    )
    (net (code "50") (name "unconnected-(IC1-RES-Pad4)") (class "Default")
      (node (ref "IC1") (pin "4") (pinfunction "RES_4") (pintype "passive+no_connect"))
    )
    (net (code "51") (name "unconnected-(M1-ADC-Pad2)") (class "Default")
      (node (ref "M1") (pin "2") (pinfunction "ADC_2") (pintype "passive+no_connect"))
    )
    (net (code "52") (name "unconnected-(M1-IO0-Pad12)") (class "Default")
      (node (ref "M1") (pin "12") (pinfunction "IO0_12") (pintype "passive+no_connect"))
    )
    (net (code "53") (name "unconnected-(M1-IO2-Pad11)") (class "Default")
      (node (ref "M1") (pin "11") (pinfunction "IO2_11") (pintype "passive+no_connect"))
    )
    (net (code "54") (name "unconnected-(M1-IO4-Pad13)") (class "Default")
      (node (ref "M1") (pin "13") (pinfunction "IO4_13") (pintype "passive+no_connect"))
    )
    (net (code "55") (name "unconnected-(M1-IO5-Pad14)") (class "Default")
      (node (ref "M1") (pin "14") (pinfunction "IO5_14") (pintype "passive+no_connect"))
    )
    (net (code "56") (name "unconnected-(M1-IO12-Pad6)") (class "Default")
      (node (ref "M1") (pin "6") (pinfunction "IO12_6") (pintype "passive+no_connect"))
    )
    (net (code "57") (name "unconnected-(M1-IO13-Pad7)") (class "Default")
      (node (ref "M1") (pin "7") (pinfunction "IO13_7") (pintype "passive+no_connect"))
    )
    (net (code "58") (name "unconnected-(M1-IO14-Pad5)") (class "Default")
      (node (ref "M1") (pin "5") (pinfunction "IO14_5") (pintype "passive+no_connect"))
    )
    (net (code "59") (name "unconnected-(M1-IO15-Pad10)") (class "Default")
      (node (ref "M1") (pin "10") (pinfunction "IO15_10") (pintype "passive+no_connect"))
    )
    (net (code "60") (name "unconnected-(M1-IO16-Pad4)") (class "Default")
      (node (ref "M1") (pin "4") (pinfunction "IO16_4") (pintype "passive+no_connect"))
    )
    (net (code "61") (name "unconnected-(P1-Pad3)") (class "Default")
      (node (ref "P1") (pin "3") (pinfunction "3_3") (pintype "passive+no_connect"))
    )
    (net (code "62") (name "unconnected-(TypeC1-Pad0)") (class "Default")
      (node (ref "TypeC1") (pin "0") (pinfunction "0_0") (pintype "passive+no_connect"))
    )
    (net (code "63") (name "unconnected-(TypeC1-Pad0)_1") (class "Default")
      (node (ref "TypeC1") (pin "0") (pinfunction "0_0") (pintype "passive+no_connect"))
    )
    (net (code "64") (name "unconnected-(TypeC1-Pad0)_2") (class "Default")
      (node (ref "TypeC1") (pin "0") (pinfunction "0_0") (pintype "passive+no_connect"))
    )
    (net (code "65") (name "unconnected-(TypeC1-Pad0)_3") (class "Default")
      (node (ref "TypeC1") (pin "0") (pinfunction "0_0") (pintype "passive+no_connect"))
    )
    (net (code "66") (name "unconnected-(TypeC1-SBU1-PadA8)") (class "Default")
      (node (ref "TypeC1") (pin "A8") (pinfunction "SBU1_A8") (pintype "passive+no_connect"))
    )
    (net (code "67") (name "unconnected-(TypeC1-SBU2-PadB8)") (class "Default")
      (node (ref "TypeC1") (pin "B8") (pinfunction "SBU2_B8") (pintype "passive+no_connect"))
    )
    (net (code "68") (name "unconnected-(U1A-NRST-Pad7)") (class "Default")
      (node (ref "U1") (pin "7") (pinfunction "NRST_7") (pintype "bidirectional"))
    )
    (net (code "69") (name "unconnected-(U1A-PA1-Pad11)") (class "Default")
      (node (ref "U1") (pin "11") (pinfunction "PA1_11") (pintype "bidirectional"))
    )
    (net (code "70") (name "unconnected-(U1A-PA11-Pad32)") (class "Default")
      (node (ref "U1") (pin "32") (pinfunction "PA11_32") (pintype "bidirectional"))
    )
    (net (code "71") (name "unconnected-(U1A-PA14-SWCLK-Pad37)") (class "Default")
      (node (ref "U1") (pin "37") (pinfunction "PA14-SWCLK_37") (pintype "bidirectional"))
    )
    (net (code "72") (name "unconnected-(U1A-PA15-Pad38)") (class "Default")
      (node (ref "U1") (pin "38") (pinfunction "PA15_38") (pintype "bidirectional"))
    )
    (net (code "73") (name "unconnected-(U1A-PB3-Pad39)") (class "Default")
      (node (ref "U1") (pin "39") (pinfunction "PB3_39") (pintype "bidirectional"))
    )
    (net (code "74") (name "unconnected-(U1A-PB5-Pad41)") (class "Default")
      (node (ref "U1") (pin "41") (pinfunction "PB5_41") (pintype "bidirectional"))
    )
    (net (code "75") (name "unconnected-(U1A-PB14-Pad27)") (class "Default")
      (node (ref "U1") (pin "27") (pinfunction "PB14_27") (pintype "bidirectional"))
    )
    (net (code "76") (name "unconnected-(U1A-PC13-TAMPER-RTC-Pad2)") (class "Default")
      (node (ref "U1") (pin "2") (pinfunction "PC13-TAMPER-RTC_2") (pintype "bidirectional"))
    )
    (net (code "77") (name "unconnected-(X1-Pad2)") (class "Default")
      (node (ref "X1") (pin "2") (pinfunction "2_2") (pintype "passive"))
    )
    (net (code "78") (name "unconnected-(X1-Pad3)") (class "Default")
      (node (ref "X1") (pin "3") (pinfunction "3_3") (pintype "passive"))
    )
  )
)
